# DSKYR1.net
KiCad netlist of a schematic drawn in EAGLE
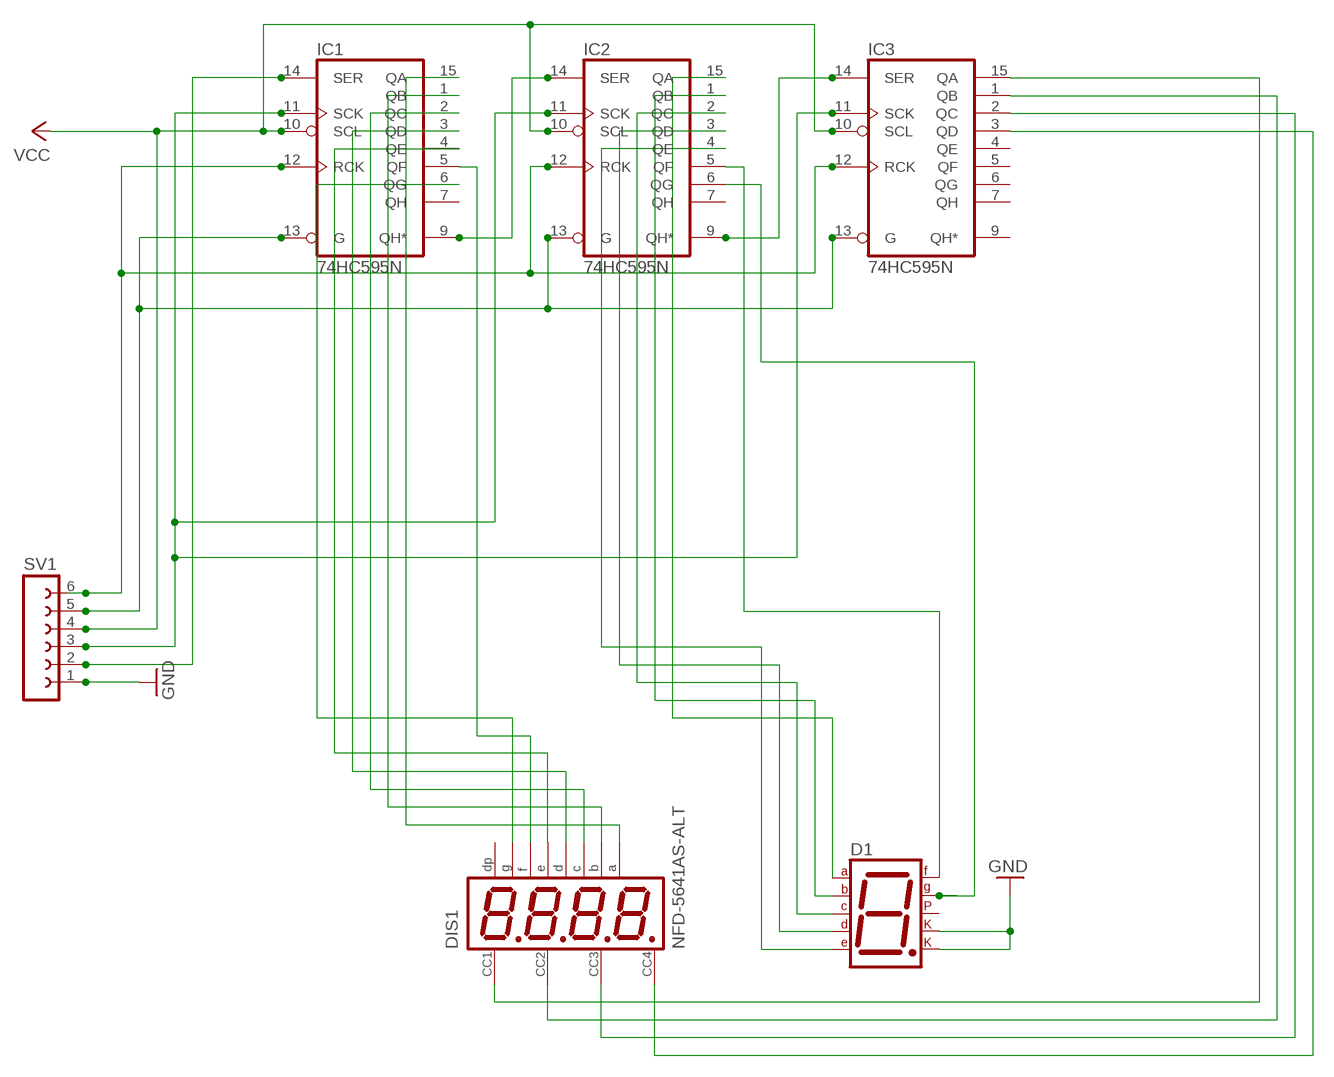
[diagram p0: schematic, sheet 1]

(export (version "E")
  (design (tool "Eeschema 10.0.6"))
  (components
    (comp (ref "D1")
      (value "7SEG-CK")
      (footprint "eagle-import:7SEG-13")
      (libsource (lib "eagle-import") (part "7SEG-CK"))
    )
    (comp (ref "DIS1")
      (value "NFD-5641AS-ALT")
      (footprint "eagle-import:NFD-5641")
      (libsource (lib "eagle-import") (part "NFD-5641AS-ALT"))
    )
    (comp (ref "IC1")
      (value "74HC595N")
      (footprint "eagle-import:DIL16")
      (libsource (lib "eagle-import") (part "74595NHC"))
    )
    (comp (ref "IC2")
      (value "74HC595N")
      (footprint "eagle-import:DIL16")
      (libsource (lib "eagle-import") (part "74595NHC"))
    )
    (comp (ref "IC3")
      (value "74HC595N")
      (footprint "eagle-import:DIL16")
      (libsource (lib "eagle-import") (part "74595NHC"))
    )
    (comp (ref "SV1")
      (value "FE06-1")
      (footprint "eagle-import:FE06")
      (libsource (lib "eagle-import") (part "FE06-1"))
    )
  )
  (nets
    (net (code "1") (name "GND") (class "Default")
      (node (ref "D1") (pin "3") (pinfunction "CK1_3") (pintype "passive"))
      (node (ref "D1") (pin "8") (pinfunction "CK2_8") (pintype "passive"))
      (node (ref "SV1") (pin "1") (pinfunction "1_1") (pintype "passive"))
    )
    (net (code "2") (name "Net-(D1-A)") (class "Default")
      (node (ref "D1") (pin "7") (pinfunction "A_7") (pintype "passive"))
      (node (ref "IC2") (pin "15") (pinfunction "QA_15") (pintype "tri_state"))
    )
    (net (code "3") (name "Net-(D1-B)") (class "Default")
      (node (ref "D1") (pin "6") (pinfunction "B_6") (pintype "passive"))
      (node (ref "IC2") (pin "1") (pinfunction "QB_1") (pintype "tri_state"))
    )
    (net (code "4") (name "Net-(D1-C)") (class "Default")
      (node (ref "D1") (pin "4") (pinfunction "C_4") (pintype "passive"))
      (node (ref "IC2") (pin "2") (pinfunction "QC_2") (pintype "tri_state"))
    )
    (net (code "5") (name "Net-(D1-D)") (class "Default")
      (node (ref "D1") (pin "2") (pinfunction "D_2") (pintype "passive"))
      (node (ref "IC2") (pin "3") (pinfunction "QD_3") (pintype "tri_state"))
    )
    (net (code "6") (name "Net-(D1-E)") (class "Default")
      (node (ref "D1") (pin "1") (pinfunction "E_1") (pintype "passive"))
      (node (ref "IC2") (pin "4") (pinfunction "QE_4") (pintype "tri_state"))
    )
    (net (code "7") (name "Net-(D1-F)") (class "Default")
      (node (ref "D1") (pin "9") (pinfunction "F_9") (pintype "passive"))
      (node (ref "IC2") (pin "5") (pinfunction "QF_5") (pintype "tri_state"))
    )
    (net (code "8") (name "Net-(D1-G)") (class "Default")
      (node (ref "D1") (pin "10") (pinfunction "G_10") (pintype "passive"))
      (node (ref "IC2") (pin "6") (pinfunction "QG_6") (pintype "tri_state"))
    )
    (net (code "9") (name "Net-(IC1A-G)") (class "Default")
      (node (ref "IC1") (pin "13") (pinfunction "G_13") (pintype "input"))
      (node (ref "IC2") (pin "13") (pinfunction "G_13") (pintype "input"))
      (node (ref "IC3") (pin "13") (pinfunction "G_13") (pintype "input"))
      (node (ref "SV1") (pin "5") (pinfunction "5_5") (pintype "passive"))
    )
    (net (code "10") (name "Net-(IC1A-QA)") (class "Default")
      (node (ref "DIS1") (pin "P$11") (pinfunction "P$11_P$11") (pintype "bidirectional"))
      (node (ref "IC1") (pin "15") (pinfunction "QA_15") (pintype "tri_state"))
    )
    (net (code "11") (name "Net-(IC1A-QB)") (class "Default")
      (node (ref "DIS1") (pin "P$7") (pinfunction "P$7_P$7") (pintype "bidirectional"))
      (node (ref "IC1") (pin "1") (pinfunction "QB_1") (pintype "tri_state"))
    )
    (net (code "12") (name "Net-(IC1A-QC)") (class "Default")
      (node (ref "DIS1") (pin "P$4") (pinfunction "P$4_P$4") (pintype "bidirectional"))
      (node (ref "IC1") (pin "2") (pinfunction "QC_2") (pintype "tri_state"))
    )
    (net (code "13") (name "Net-(IC1A-QD)") (class "Default")
      (node (ref "DIS1") (pin "P$2") (pinfunction "P$2_P$2") (pintype "bidirectional"))
      (node (ref "IC1") (pin "3") (pinfunction "QD_3") (pintype "tri_state"))
    )
    (net (code "14") (name "Net-(IC1A-QE)") (class "Default")
      (node (ref "DIS1") (pin "P$1") (pinfunction "P$1_P$1") (pintype "bidirectional"))
      (node (ref "IC1") (pin "4") (pinfunction "QE_4") (pintype "tri_state"))
    )
    (net (code "15") (name "Net-(IC1A-QF)") (class "Default")
      (node (ref "DIS1") (pin "P$10") (pinfunction "P$10_P$10") (pintype "bidirectional"))
      (node (ref "IC1") (pin "5") (pinfunction "QF_5") (pintype "tri_state"))
    )
    (net (code "16") (name "Net-(IC1A-QG)") (class "Default")
      (node (ref "DIS1") (pin "P$5") (pinfunction "P$5_P$5") (pintype "bidirectional"))
      (node (ref "IC1") (pin "6") (pinfunction "QG_6") (pintype "tri_state"))
    )
    (net (code "17") (name "Net-(IC1A-QH*)") (class "Default")
      (node (ref "IC1") (pin "9") (pinfunction "QH*_9") (pintype "tri_state"))
      (node (ref "IC2") (pin "14") (pinfunction "SER_14") (pintype "input"))
    )
    (net (code "18") (name "Net-(IC1A-RCK)") (class "Default")
      (node (ref "IC1") (pin "12") (pinfunction "RCK_12") (pintype "input"))
      (node (ref "IC2") (pin "12") (pinfunction "RCK_12") (pintype "input"))
      (node (ref "IC3") (pin "12") (pinfunction "RCK_12") (pintype "input"))
      (node (ref "SV1") (pin "6") (pinfunction "6_6") (pintype "passive"))
    )
    (net (code "19") (name "Net-(IC1A-SCK)") (class "Default")
      (node (ref "IC1") (pin "11") (pinfunction "SCK_11") (pintype "input"))
      (node (ref "IC2") (pin "11") (pinfunction "SCK_11") (pintype "input"))
      (node (ref "IC3") (pin "11") (pinfunction "SCK_11") (pintype "input"))
      (node (ref "SV1") (pin "3") (pinfunction "3_3") (pintype "passive"))
    )
    (net (code "20") (name "Net-(IC1A-SER)") (class "Default")
      (node (ref "IC1") (pin "14") (pinfunction "SER_14") (pintype "input"))
      (node (ref "SV1") (pin "2") (pinfunction "2_2") (pintype "passive"))
    )
    (net (code "21") (name "Net-(IC2A-QH*)") (class "Default")
      (node (ref "IC2") (pin "9") (pinfunction "QH*_9") (pintype "tri_state"))
      (node (ref "IC3") (pin "14") (pinfunction "SER_14") (pintype "input"))
    )
    (net (code "22") (name "Net-(IC3A-QA)") (class "Default")
      (node (ref "DIS1") (pin "P$12") (pinfunction "P$12_P$12") (pintype "bidirectional"))
      (node (ref "IC3") (pin "15") (pinfunction "QA_15") (pintype "tri_state"))
    )
    (net (code "23") (name "Net-(IC3A-QB)") (class "Default")
      (node (ref "DIS1") (pin "P$9") (pinfunction "P$9_P$9") (pintype "bidirectional"))
      (node (ref "IC3") (pin "1") (pinfunction "QB_1") (pintype "tri_state"))
    )
    (net (code "24") (name "Net-(IC3A-QC)") (class "Default")
      (node (ref "DIS1") (pin "P$8") (pinfunction "P$8_P$8") (pintype "bidirectional"))
      (node (ref "IC3") (pin "2") (pinfunction "QC_2") (pintype "tri_state"))
    )
    (net (code "25") (name "Net-(IC3A-QD)") (class "Default")
      (node (ref "DIS1") (pin "P$6") (pinfunction "P$6_P$6") (pintype "bidirectional"))
      (node (ref "IC3") (pin "3") (pinfunction "QD_3") (pintype "tri_state"))
    )
    (net (code "26") (name "VCC") (class "Default")
      (node (ref "IC1") (pin "10") (pinfunction "SCL_10") (pintype "input"))
      (node (ref "IC2") (pin "10") (pinfunction "SCL_10") (pintype "input"))
      (node (ref "IC3") (pin "10") (pinfunction "SCL_10") (pintype "input"))
      (node (ref "SV1") (pin "4") (pinfunction "4_4") (pintype "passive"))
    )
    (net (code "27") (name "unconnected-(D1-DP-Pad5)") (class "Default")
      (node (ref "D1") (pin "5") (pinfunction "DP_5") (pintype "passive"))
    )
    (net (code "28") (name "unconnected-(DIS1-PadP$3)") (class "Default")
      (node (ref "DIS1") (pin "P$3") (pinfunction "P$3_P$3") (pintype "bidirectional"))
    )
    (net (code "29") (name "unconnected-(IC1A-QH-Pad7)") (class "Default")
      (node (ref "IC1") (pin "7") (pinfunction "QH_7") (pintype "tri_state"))
    )
    (net (code "30") (name "unconnected-(IC2A-QH-Pad7)") (class "Default")
      (node (ref "IC2") (pin "7") (pinfunction "QH_7") (pintype "tri_state"))
    )
    (net (code "31") (name "unconnected-(IC3A-QE-Pad4)") (class "Default")
      (node (ref "IC3") (pin "4") (pinfunction "QE_4") (pintype "tri_state"))
    )
    (net (code "32") (name "unconnected-(IC3A-QF-Pad5)") (class "Default")
      (node (ref "IC3") (pin "5") (pinfunction "QF_5") (pintype "tri_state"))
    )
    (net (code "33") (name "unconnected-(IC3A-QG-Pad6)") (class "Default")
      (node (ref "IC3") (pin "6") (pinfunction "QG_6") (pintype "tri_state"))
    )
    (net (code "34") (name "unconnected-(IC3A-QH*-Pad9)") (class "Default")
      (node (ref "IC3") (pin "9") (pinfunction "QH*_9") (pintype "tri_state"))
    )
    (net (code "35") (name "unconnected-(IC3A-QH-Pad7)") (class "Default")
      (node (ref "IC3") (pin "7") (pinfunction "QH_7") (pintype "tri_state"))
    )
  )
)
